# StepDown_V1.net
KiCad netlist of a schematic drawn in EAGLE
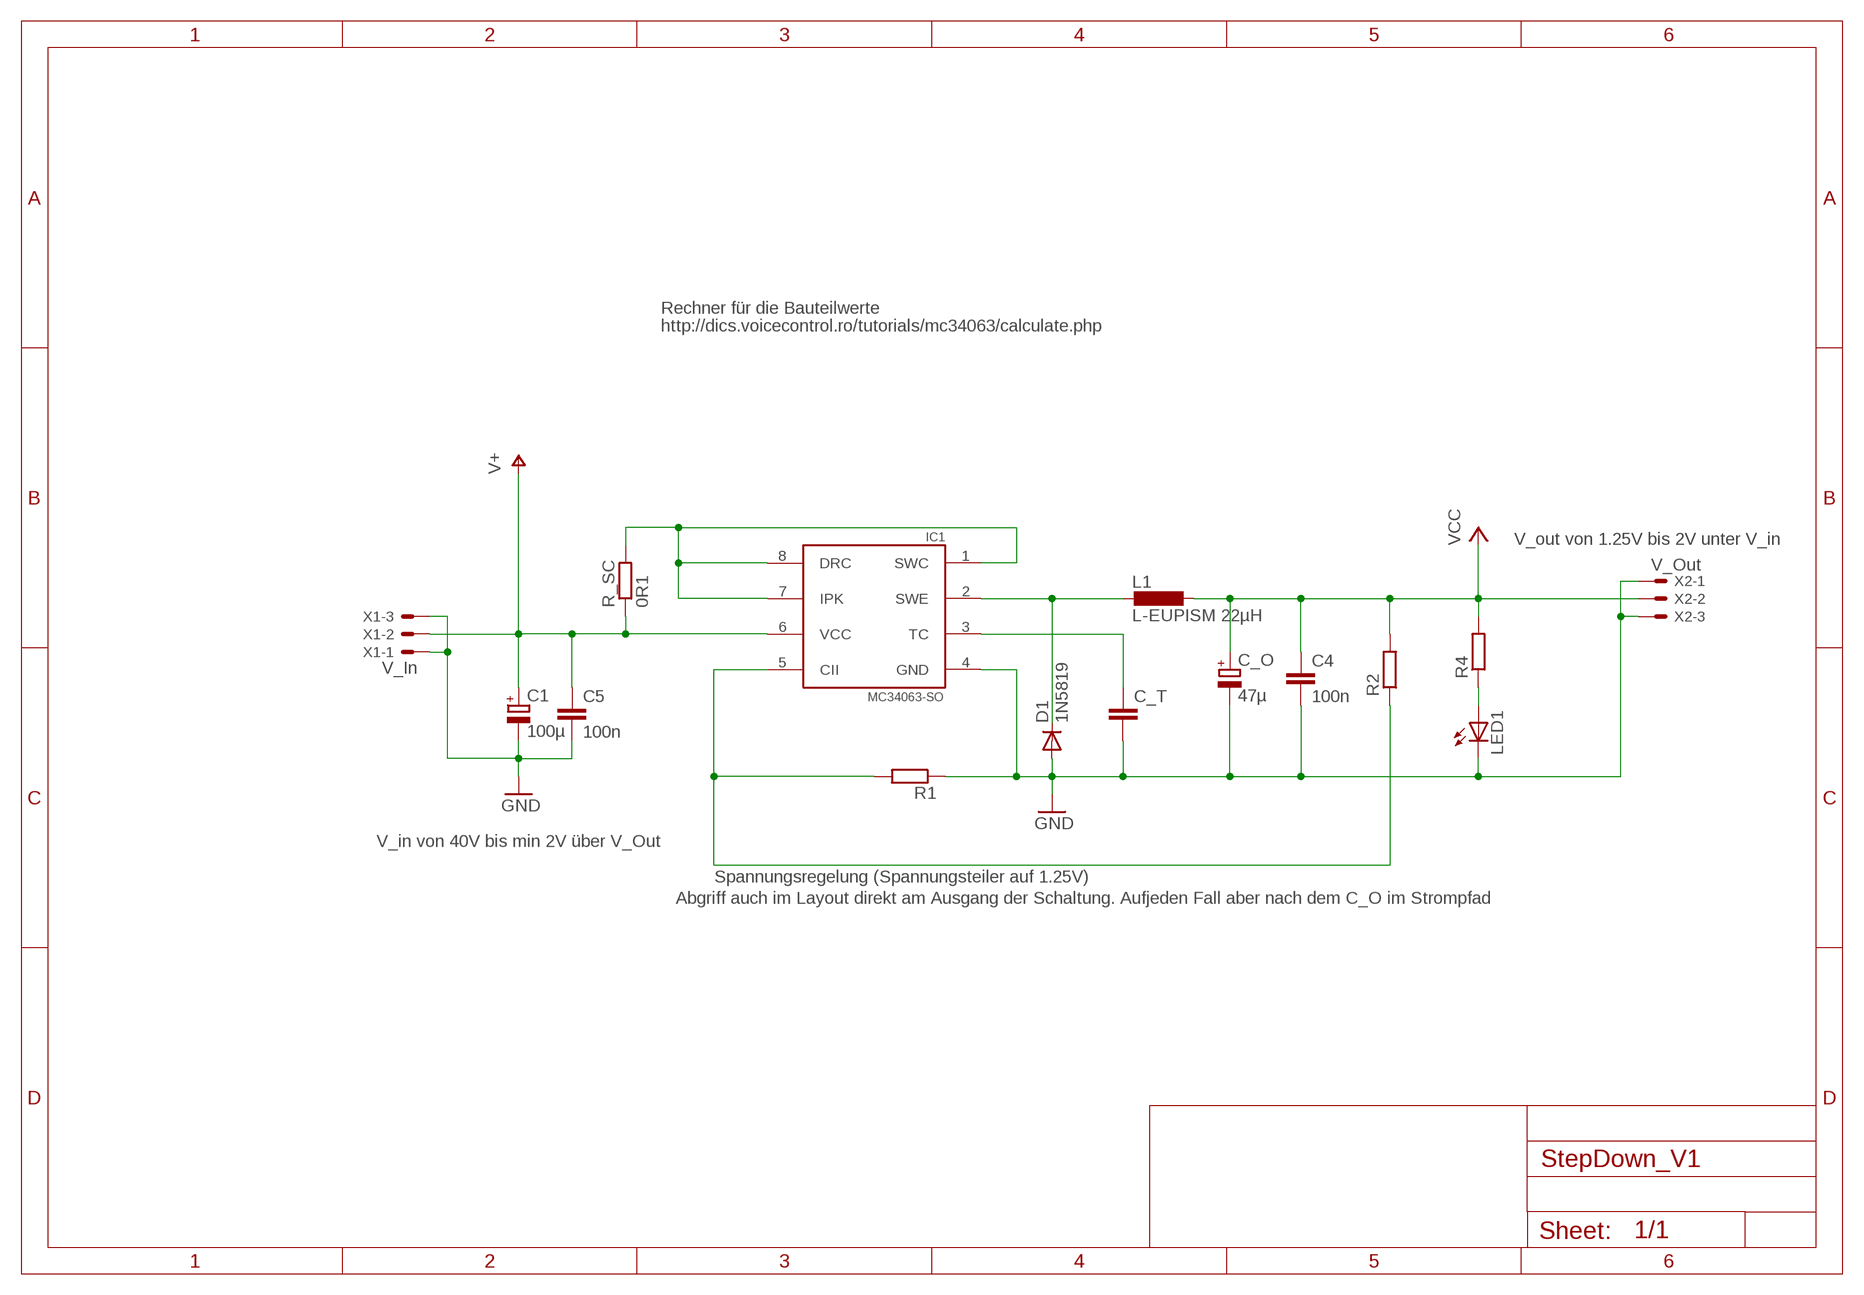
[diagram p0: schematic, sheet 1]

(export (version "E")
  (design (tool "Eeschema 10.0.6"))
  (components
    (comp (ref "C1")
      (value "100µ")
      (footprint "eagle-import:E2,5-7")
      (libsource (lib "eagle-import") (part "CPOL-EUE2.5-7"))
    )
    (comp (ref "C4")
      (value "100n")
      (footprint "eagle-import:C1206")
      (libsource (lib "eagle-import") (part "C-EUC1206"))
    )
    (comp (ref "C5")
      (value "100n")
      (footprint "eagle-import:C1206")
      (libsource (lib "eagle-import") (part "C-EUC1206"))
    )
    (comp (ref "C_O")
      (value "47µ")
      (footprint "eagle-import:E2,5-7")
      (libsource (lib "eagle-import") (part "CPOL-EUE2.5-7"))
    )
    (comp (ref "C_T")
      (value "C-EUC1206")
      (footprint "eagle-import:C1206")
      (libsource (lib "eagle-import") (part "C-EUC1206"))
    )
    (comp (ref "D1")
      (value "1N5819")
      (footprint "eagle-import:DO41-10")
      (libsource (lib "eagle-import") (part "1N4933"))
    )
    (comp (ref "IC1")
      (value "MC34063-SO")
      (footprint "eagle-import:SO8")
      (libsource (lib "eagle-import") (part "MC34063-SO"))
    )
    (comp (ref "L1")
      (value "L-EUPISM 22µH")
      (footprint "eagle-import:PISM")
      (libsource (lib "eagle-import") (part "L-EUPISM"))
    )
    (comp (ref "LED1")
      (value "LEDSML1206")
      (footprint "eagle-import:SML1206")
      (libsource (lib "eagle-import") (part "LEDSML1206"))
    )
    (comp (ref "R1")
      (value "R-EU_R1206")
      (footprint "eagle-import:R1206")
      (libsource (lib "eagle-import") (part "R-EU_R1206"))
    )
    (comp (ref "R2")
      (value "R-EU_R1206")
      (footprint "eagle-import:R1206")
      (libsource (lib "eagle-import") (part "R-EU_R1206"))
    )
    (comp (ref "R4")
      (value "R-EU_R1206")
      (footprint "eagle-import:R1206")
      (libsource (lib "eagle-import") (part "R-EU_R1206"))
    )
    (comp (ref "R_SC")
      (value "0R1")
      (footprint "eagle-import:R1206")
      (libsource (lib "eagle-import") (part "R-EU_R1206"))
    )
    (comp (ref "X1")
      (value "V_In")
      (footprint "eagle-import:22-23-2031")
      (fields (field (name "MF") "MOLEX") (field (name "MPN") "22-23-2031"))
      (libsource (lib "eagle-import") (part "22-23-2031"))
    )
    (comp (ref "X2")
      (value "V_Out")
      (footprint "eagle-import:22-23-2031")
      (fields (field (name "MF") "MOLEX") (field (name "MPN") "22-23-2031"))
      (libsource (lib "eagle-import") (part "22-23-2031"))
    )
  )
  (nets
    (net (code "1") (name "GND") (class "Default")
      (node (ref "C1") (pin "-") (pinfunction "-_-") (pintype "passive"))
      (node (ref "C4") (pin "2") (pinfunction "2_2") (pintype "passive"))
      (node (ref "C5") (pin "2") (pinfunction "2_2") (pintype "passive"))
      (node (ref "C_O") (pin "-") (pinfunction "-_-") (pintype "passive"))
      (node (ref "C_T") (pin "2") (pinfunction "2_2") (pintype "passive"))
      (node (ref "D1") (pin "A") (pinfunction "A_A") (pintype "passive"))
      (node (ref "IC1") (pin "4") (pinfunction "GND_4") (pintype "power_in"))
      (node (ref "LED1") (pin "C") (pinfunction "C_C") (pintype "passive"))
      (node (ref "R1") (pin "1") (pinfunction "1_1") (pintype "passive"))
      (node (ref "X1") (pin "1") (pinfunction "S_1") (pintype "passive"))
      (node (ref "X1") (pin "3") (pinfunction "S_3") (pintype "passive"))
      (node (ref "X2") (pin "1") (pinfunction "S_1") (pintype "passive"))
      (node (ref "X2") (pin "3") (pinfunction "S_3") (pintype "passive"))
    )
    (net (code "2") (name "Net-(IC1-CII)") (class "Default")
      (node (ref "IC1") (pin "5") (pinfunction "CII_5") (pintype "bidirectional"))
      (node (ref "R1") (pin "2") (pinfunction "2_2") (pintype "passive"))
      (node (ref "R2") (pin "1") (pinfunction "1_1") (pintype "passive"))
    )
    (net (code "3") (name "Net-(IC1-DRC)") (class "Default")
      (node (ref "IC1") (pin "1") (pinfunction "SWC_1") (pintype "bidirectional"))
      (node (ref "IC1") (pin "7") (pinfunction "IPK_7") (pintype "bidirectional"))
      (node (ref "IC1") (pin "8") (pinfunction "DRC_8") (pintype "bidirectional"))
      (node (ref "R_SC") (pin "2") (pinfunction "2_2") (pintype "passive"))
    )
    (net (code "4") (name "Net-(IC1-SWE)") (class "Default")
      (node (ref "D1") (pin "C") (pinfunction "C_C") (pintype "passive"))
      (node (ref "IC1") (pin "2") (pinfunction "SWE_2") (pintype "bidirectional"))
      (node (ref "L1") (pin "2") (pinfunction "2_2") (pintype "passive"))
    )
    (net (code "5") (name "Net-(IC1-TC)") (class "Default")
      (node (ref "C_T") (pin "1") (pinfunction "1_1") (pintype "passive"))
      (node (ref "IC1") (pin "3") (pinfunction "TC_3") (pintype "bidirectional"))
    )
    (net (code "6") (name "Net-(LED1-PadA)") (class "Default")
      (node (ref "LED1") (pin "A") (pinfunction "A_A") (pintype "passive"))
      (node (ref "R4") (pin "1") (pinfunction "1_1") (pintype "passive"))
    )
    (net (code "7") (name "V+") (class "Default")
      (node (ref "C1") (pin "+") (pinfunction "+_+") (pintype "passive"))
      (node (ref "C5") (pin "1") (pinfunction "1_1") (pintype "passive"))
      (node (ref "IC1") (pin "6") (pinfunction "VCC_6") (pintype "bidirectional"))
      (node (ref "R_SC") (pin "1") (pinfunction "1_1") (pintype "passive"))
      (node (ref "X1") (pin "2") (pinfunction "S_2") (pintype "passive"))
    )
    (net (code "8") (name "VCC") (class "Default")
      (node (ref "C4") (pin "1") (pinfunction "1_1") (pintype "passive"))
      (node (ref "C_O") (pin "+") (pinfunction "+_+") (pintype "passive"))
      (node (ref "L1") (pin "1") (pinfunction "1_1") (pintype "passive"))
      (node (ref "R2") (pin "2") (pinfunction "2_2") (pintype "passive"))
      (node (ref "R4") (pin "2") (pinfunction "2_2") (pintype "passive"))
      (node (ref "X2") (pin "2") (pinfunction "S_2") (pintype "passive"))
    )
  )
)
